# NANO-walkie-talkie-JLC1.net
KiCad netlist of a schematic drawn in EAGLE
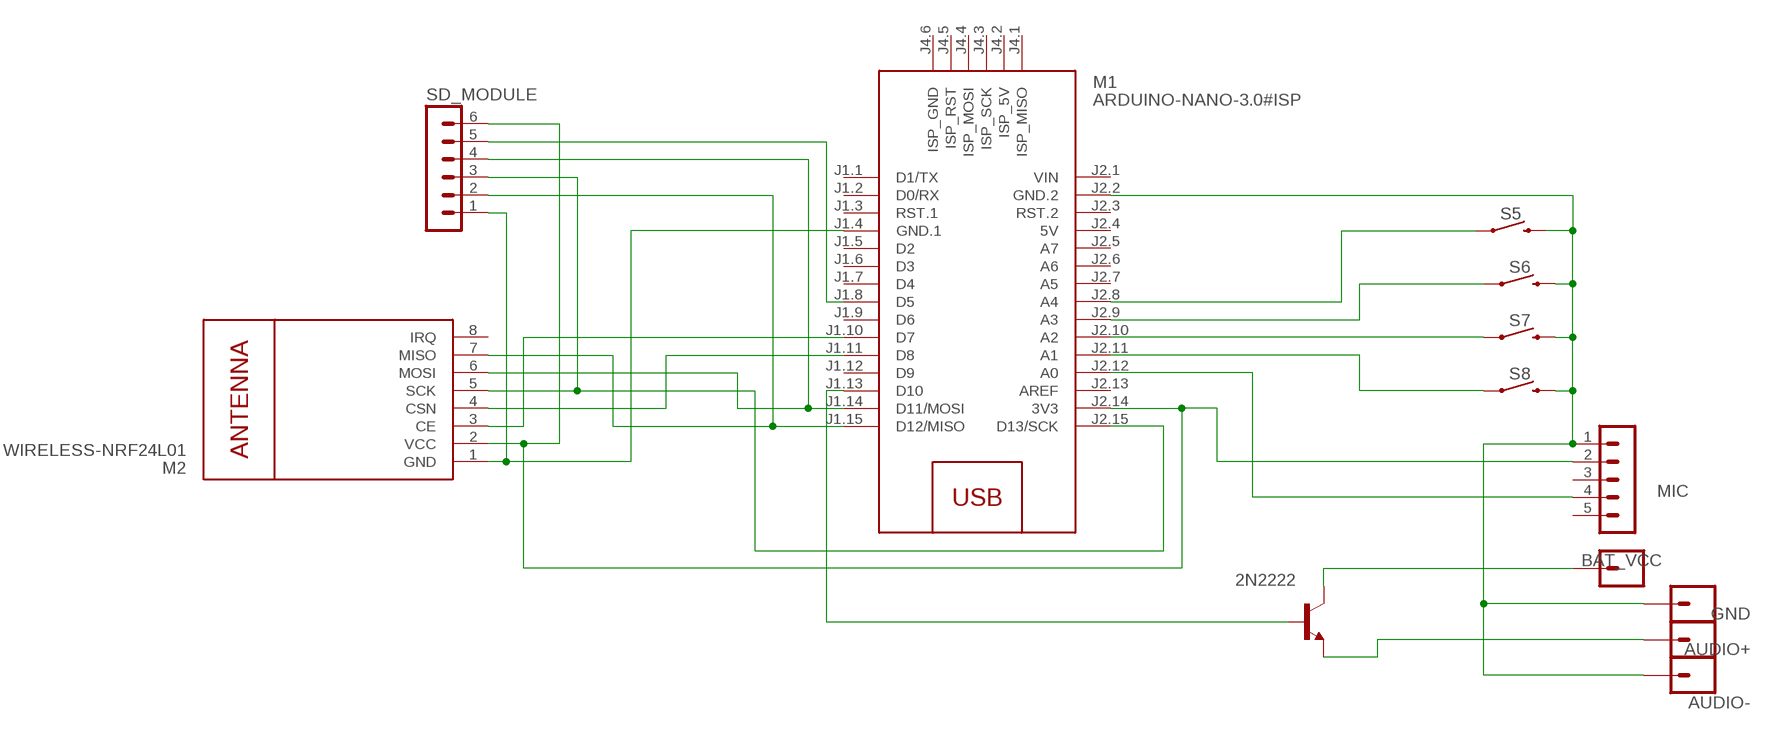
[diagram p0: schematic, sheet 1]

(export (version "E")
  (design (tool "Eeschema 10.0.6"))
  (components
    (comp (ref "AUDIO+")
      (value "CONN_01PTH_LONGPAD")
      (footprint "eagle-import:1X01_LONGPAD")
      (libsource (lib "eagle-import") (part "CONN_01PTH_LONGPAD"))
    )
    (comp (ref "AUDIO-")
      (value "CONN_01PTH_LONGPAD")
      (footprint "eagle-import:1X01_LONGPAD")
      (libsource (lib "eagle-import") (part "CONN_01PTH_LONGPAD"))
    )
    (comp (ref "BAT_VCC")
      (value "CONN_01PTH_LONGPAD")
      (footprint "eagle-import:1X01_LONGPAD")
      (libsource (lib "eagle-import") (part "CONN_01PTH_LONGPAD"))
    )
    (comp (ref "GND")
      (value "CONN_01PTH_LONGPAD")
      (footprint "eagle-import:1X01_LONGPAD")
      (libsource (lib "eagle-import") (part "CONN_01PTH_LONGPAD"))
    )
    (comp (ref "M1")
      (value "ARDUINO-NANO-3.0#ISP")
      (footprint "eagle-import:ARDUINO-NANO-3.0#ISP")
      (libsource (lib "eagle-import") (part "ARDUINO-NANO-3.0#ISP"))
    )
    (comp (ref "M2")
      (value "WIRELESS-NRF24L01")
      (footprint "eagle-import:WIRELESS-NRF24L01")
      (libsource (lib "eagle-import") (part "WIRELESS-NRF24L01"))
    )
    (comp (ref "MIC")
      (value "MA05-1")
      (footprint "eagle-import:MA05-1")
      (libsource (lib "eagle-import") (part "MA05-1"))
    )
    (comp (ref "S5")
      (value "MOMENTARY-SWITCH-SPST-SMD-6.0X3.5MM")
      (footprint "eagle-import:TACTILE_SWITCH_SMD_6.0X3.5MM")
      (libsource (lib "eagle-import") (part "MOMENTARY-SWITCH-SPST-SMD-6.0X3.5MM"))
    )
    (comp (ref "S6")
      (value "MOMENTARY-SWITCH-SPST-SMD-6.0X3.5MM")
      (footprint "eagle-import:TACTILE_SWITCH_SMD_6.0X3.5MM")
      (libsource (lib "eagle-import") (part "MOMENTARY-SWITCH-SPST-SMD-6.0X3.5MM"))
    )
    (comp (ref "S7")
      (value "MOMENTARY-SWITCH-SPST-SMD-6.0X3.5MM")
      (footprint "eagle-import:TACTILE_SWITCH_SMD_6.0X3.5MM")
      (libsource (lib "eagle-import") (part "MOMENTARY-SWITCH-SPST-SMD-6.0X3.5MM"))
    )
    (comp (ref "S8")
      (value "MOMENTARY-SWITCH-SPST-SMD-6.0X3.5MM")
      (footprint "eagle-import:TACTILE_SWITCH_SMD_6.0X3.5MM")
      (libsource (lib "eagle-import") (part "MOMENTARY-SWITCH-SPST-SMD-6.0X3.5MM"))
    )
    (comp (ref "SD_MODULE")
      (value "MA06-1")
      (footprint "eagle-import:MA06-1")
      (libsource (lib "eagle-import") (part "MA06-1"))
    )
    (comp (ref "T1")
      (value "2N2222")
      (footprint "eagle-import:TO18")
      (libsource (lib "eagle-import") (part "2N2222"))
    )
  )
  (nets
    (net (code "1") (name "/5V") (class "Default")
      (node (ref "M1") (pin "J2.4") (pinfunction "5V_J2.4") (pintype "power_in"))
    )
    (net (code "2") (name "/VIN") (class "Default")
      (node (ref "M1") (pin "J2.1") (pinfunction "VIN_J2.1") (pintype "power_in"))
    )
    (net (code "3") (name "Net-(M1-3V3)") (class "Default")
      (node (ref "M1") (pin "J2.14") (pinfunction "3V3_J2.14") (pintype "power_in"))
      (node (ref "M2") (pin "2") (pinfunction "VCC_2") (pintype "power_in"))
      (node (ref "MIC") (pin "2") (pinfunction "2_2") (pintype "passive"))
      (node (ref "SD_MODULE") (pin "6") (pinfunction "6_6") (pintype "passive"))
    )
    (net (code "4") (name "Net-(M1-A0)") (class "Default")
      (node (ref "M1") (pin "J2.12") (pinfunction "A0_J2.12") (pintype "bidirectional"))
      (node (ref "MIC") (pin "4") (pinfunction "4_4") (pintype "passive"))
    )
    (net (code "5") (name "Net-(M1-A1)") (class "Default")
      (node (ref "M1") (pin "J2.11") (pinfunction "A1_J2.11") (pintype "bidirectional"))
      (node (ref "S8") (pin "1") (pinfunction "1_1") (pintype "passive"))
    )
    (net (code "6") (name "Net-(M1-A2)") (class "Default")
      (node (ref "M1") (pin "J2.10") (pinfunction "A2_J2.10") (pintype "bidirectional"))
      (node (ref "S7") (pin "1") (pinfunction "1_1") (pintype "passive"))
    )
    (net (code "7") (name "Net-(M1-A3)") (class "Default")
      (node (ref "M1") (pin "J2.9") (pinfunction "A3_J2.9") (pintype "bidirectional"))
      (node (ref "S6") (pin "1") (pinfunction "1_1") (pintype "passive"))
    )
    (net (code "8") (name "Net-(M1-A4)") (class "Default")
      (node (ref "M1") (pin "J2.8") (pinfunction "A4_J2.8") (pintype "bidirectional"))
      (node (ref "S5") (pin "1") (pinfunction "1_1") (pintype "passive"))
    )
    (net (code "9") (name "Net-(M1-D5)") (class "Default")
      (node (ref "M1") (pin "J1.8") (pinfunction "D5_J1.8") (pintype "bidirectional"))
      (node (ref "SD_MODULE") (pin "5") (pinfunction "5_5") (pintype "passive"))
    )
    (net (code "10") (name "Net-(M1-D7)") (class "Default")
      (node (ref "M1") (pin "J1.10") (pinfunction "D7_J1.10") (pintype "bidirectional"))
      (node (ref "M2") (pin "3") (pinfunction "CE_3") (pintype "bidirectional"))
    )
    (net (code "11") (name "Net-(M1-D8)") (class "Default")
      (node (ref "M1") (pin "J1.11") (pinfunction "D8_J1.11") (pintype "bidirectional"))
      (node (ref "M2") (pin "4") (pinfunction "CSN_4") (pintype "bidirectional"))
    )
    (net (code "12") (name "Net-(M1-D10)") (class "Default")
      (node (ref "M1") (pin "J1.13") (pinfunction "D10_J1.13") (pintype "bidirectional"))
      (node (ref "T1") (pin "2") (pinfunction "B_2") (pintype "passive"))
    )
    (net (code "13") (name "Net-(M1-D11{slash}MOSI)") (class "Default")
      (node (ref "M1") (pin "J1.14") (pinfunction "D11/MOSI_J1.14") (pintype "bidirectional"))
      (node (ref "M2") (pin "6") (pinfunction "MOSI_6") (pintype "bidirectional"))
      (node (ref "SD_MODULE") (pin "4") (pinfunction "4_4") (pintype "passive"))
    )
    (net (code "14") (name "Net-(M1-D12{slash}MISO)") (class "Default")
      (node (ref "M1") (pin "J1.15") (pinfunction "D12/MISO_J1.15") (pintype "bidirectional"))
      (node (ref "M2") (pin "7") (pinfunction "MISO_7") (pintype "bidirectional"))
      (node (ref "SD_MODULE") (pin "2") (pinfunction "2_2") (pintype "passive"))
    )
    (net (code "15") (name "Net-(M1-D13{slash}SCK)") (class "Default")
      (node (ref "M1") (pin "J2.15") (pinfunction "D13/SCK_J2.15") (pintype "bidirectional"))
      (node (ref "M2") (pin "5") (pinfunction "SCK_5") (pintype "bidirectional"))
      (node (ref "SD_MODULE") (pin "3") (pinfunction "3_3") (pintype "passive"))
    )
    (net (code "16") (name "Net-(M1-GND.1)") (class "Default")
      (node (ref "M1") (pin "J1.4") (pinfunction "GND.1_J1.4") (pintype "power_in"))
      (node (ref "M2") (pin "1") (pinfunction "GND_1") (pintype "power_in"))
      (node (ref "SD_MODULE") (pin "1") (pinfunction "1_1") (pintype "passive"))
    )
    (net (code "17") (name "Net-(M1-GND.2)") (class "Default")
      (node (ref "AUDIO-") (pin "1") (pinfunction "1_1") (pintype "passive"))
      (node (ref "GND") (pin "1") (pinfunction "1_1") (pintype "passive"))
      (node (ref "M1") (pin "J2.2") (pinfunction "GND.2_J2.2") (pintype "power_in"))
      (node (ref "MIC") (pin "1") (pinfunction "1_1") (pintype "passive"))
      (node (ref "S5") (pin "2") (pinfunction "2_2") (pintype "passive"))
      (node (ref "S6") (pin "2") (pinfunction "2_2") (pintype "passive"))
      (node (ref "S7") (pin "2") (pinfunction "2_2") (pintype "passive"))
      (node (ref "S8") (pin "2") (pinfunction "2_2") (pintype "passive"))
    )
    (net (code "18") (name "Net-(T1-C)") (class "Default")
      (node (ref "BAT_VCC") (pin "1") (pinfunction "1_1") (pintype "passive"))
      (node (ref "T1") (pin "3") (pinfunction "C_3") (pintype "passive"))
    )
    (net (code "19") (name "Net-(T1-E)") (class "Default")
      (node (ref "AUDIO+") (pin "1") (pinfunction "1_1") (pintype "passive"))
      (node (ref "T1") (pin "1") (pinfunction "E_1") (pintype "passive"))
    )
    (net (code "20") (name "unconnected-(M1-A5-PadJ2.7)") (class "Default")
      (node (ref "M1") (pin "J2.7") (pinfunction "A5_J2.7") (pintype "bidirectional"))
    )
    (net (code "21") (name "unconnected-(M1-A6-PadJ2.6)") (class "Default")
      (node (ref "M1") (pin "J2.6") (pinfunction "A6_J2.6") (pintype "bidirectional"))
    )
    (net (code "22") (name "unconnected-(M1-A7-PadJ2.5)") (class "Default")
      (node (ref "M1") (pin "J2.5") (pinfunction "A7_J2.5") (pintype "bidirectional"))
    )
    (net (code "23") (name "unconnected-(M1-AREF-PadJ2.13)") (class "Default")
      (node (ref "M1") (pin "J2.13") (pinfunction "AREF_J2.13") (pintype "bidirectional"))
    )
    (net (code "24") (name "unconnected-(M1-D0{slash}RX-PadJ1.2)") (class "Default")
      (node (ref "M1") (pin "J1.2") (pinfunction "D0/RX_J1.2") (pintype "bidirectional"))
    )
    (net (code "25") (name "unconnected-(M1-D1{slash}TX-PadJ1.1)") (class "Default")
      (node (ref "M1") (pin "J1.1") (pinfunction "D1/TX_J1.1") (pintype "bidirectional"))
    )
    (net (code "26") (name "unconnected-(M1-D2-PadJ1.5)") (class "Default")
      (node (ref "M1") (pin "J1.5") (pinfunction "D2_J1.5") (pintype "bidirectional"))
    )
    (net (code "27") (name "unconnected-(M1-D3-PadJ1.6)") (class "Default")
      (node (ref "M1") (pin "J1.6") (pinfunction "D3_J1.6") (pintype "bidirectional"))
    )
    (net (code "28") (name "unconnected-(M1-D4-PadJ1.7)") (class "Default")
      (node (ref "M1") (pin "J1.7") (pinfunction "D4_J1.7") (pintype "bidirectional"))
    )
    (net (code "29") (name "unconnected-(M1-D6-PadJ1.9)") (class "Default")
      (node (ref "M1") (pin "J1.9") (pinfunction "D6_J1.9") (pintype "bidirectional"))
    )
    (net (code "30") (name "unconnected-(M1-D9-PadJ1.12)") (class "Default")
      (node (ref "M1") (pin "J1.12") (pinfunction "D9_J1.12") (pintype "bidirectional"))
    )
    (net (code "31") (name "unconnected-(M1-ISP_5V-PadJ4.2)") (class "Default")
      (node (ref "M1") (pin "J4.2") (pinfunction "ISP_5V_J4.2") (pintype "bidirectional"))
    )
    (net (code "32") (name "unconnected-(M1-ISP_GND-PadJ4.6)") (class "Default")
      (node (ref "M1") (pin "J4.6") (pinfunction "ISP_GND_J4.6") (pintype "bidirectional"))
    )
    (net (code "33") (name "unconnected-(M1-ISP_MISO-PadJ4.1)") (class "Default")
      (node (ref "M1") (pin "J4.1") (pinfunction "ISP_MISO_J4.1") (pintype "bidirectional"))
    )
    (net (code "34") (name "unconnected-(M1-ISP_MOSI-PadJ4.4)") (class "Default")
      (node (ref "M1") (pin "J4.4") (pinfunction "ISP_MOSI_J4.4") (pintype "bidirectional"))
    )
    (net (code "35") (name "unconnected-(M1-ISP_RST-PadJ4.5)") (class "Default")
      (node (ref "M1") (pin "J4.5") (pinfunction "ISP_RST_J4.5") (pintype "bidirectional"))
    )
    (net (code "36") (name "unconnected-(M1-ISP_SCK-PadJ4.3)") (class "Default")
      (node (ref "M1") (pin "J4.3") (pinfunction "ISP_SCK_J4.3") (pintype "bidirectional"))
    )
    (net (code "37") (name "unconnected-(M1-RST.1-PadJ1.3)") (class "Default")
      (node (ref "M1") (pin "J1.3") (pinfunction "RST.1_J1.3") (pintype "bidirectional"))
    )
    (net (code "38") (name "unconnected-(M1-RST.2-PadJ2.3)") (class "Default")
      (node (ref "M1") (pin "J2.3") (pinfunction "RST.2_J2.3") (pintype "bidirectional"))
    )
    (net (code "39") (name "unconnected-(M2-IRQ-Pad8)") (class "Default")
      (node (ref "M2") (pin "8") (pinfunction "IRQ_8") (pintype "bidirectional"))
    )
    (net (code "40") (name "unconnected-(MIC-Pad3)") (class "Default")
      (node (ref "MIC") (pin "3") (pinfunction "3_3") (pintype "passive"))
    )
    (net (code "41") (name "unconnected-(MIC-Pad5)") (class "Default")
      (node (ref "MIC") (pin "5") (pinfunction "5_5") (pintype "passive"))
    )
  )
)
